# sanro.net
KiCad netlist of a schematic drawn in EAGLE
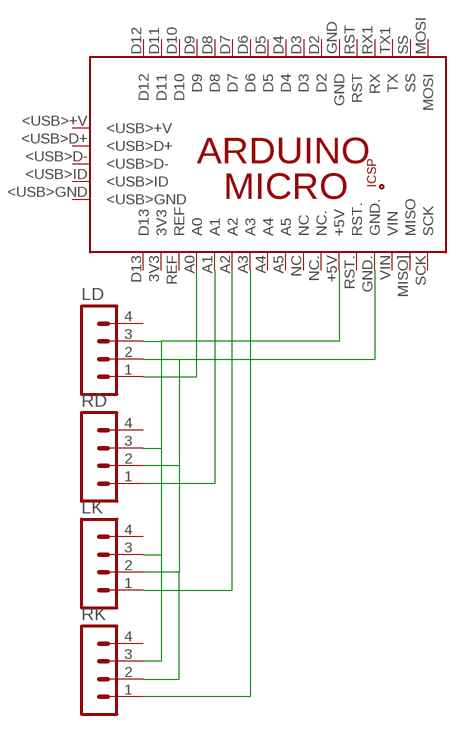
[diagram p0: schematic, sheet 1]

(export (version "E")
  (design (tool "Eeschema 10.0.6"))
  (components
    (comp (ref "LD")
      (value "MA04-1")
      (footprint "eagle-import:MA04-1")
      (libsource (lib "eagle-import") (part "MA04-1"))
    )
    (comp (ref "LK")
      (value "MA04-1")
      (footprint "eagle-import:MA04-1")
      (libsource (lib "eagle-import") (part "MA04-1"))
    )
    (comp (ref "PCB1")
      (value "ARDUINO_MICRO")
      (footprint "eagle-import:ARDUINO_MICRO")
      (libsource (lib "eagle-import") (part "ARDUINO_MICRO"))
    )
    (comp (ref "RD")
      (value "MA04-1")
      (footprint "eagle-import:MA04-1")
      (libsource (lib "eagle-import") (part "MA04-1"))
    )
    (comp (ref "RK")
      (value "MA04-1")
      (footprint "eagle-import:MA04-1")
      (libsource (lib "eagle-import") (part "MA04-1"))
    )
  )
  (nets
    (net (code "1") (name "Net-(LD-Pad1)") (class "Default")
      (node (ref "LD") (pin "1") (pinfunction "1_1") (pintype "passive"))
      (node (ref "PCB1") (pin "A0") (pinfunction "A0_A0") (pintype "bidirectional"))
    )
    (net (code "2") (name "Net-(LD-Pad2)") (class "Default")
      (node (ref "LD") (pin "2") (pinfunction "2_2") (pintype "passive"))
      (node (ref "LK") (pin "2") (pinfunction "2_2") (pintype "passive"))
      (node (ref "PCB1") (pin "GND.") (pinfunction "GND._GND.") (pintype "bidirectional"))
      (node (ref "RD") (pin "2") (pinfunction "2_2") (pintype "passive"))
      (node (ref "RK") (pin "2") (pinfunction "2_2") (pintype "passive"))
    )
    (net (code "3") (name "Net-(LD-Pad3)") (class "Default")
      (node (ref "LD") (pin "3") (pinfunction "3_3") (pintype "passive"))
      (node (ref "LK") (pin "3") (pinfunction "3_3") (pintype "passive"))
      (node (ref "PCB1") (pin "+5V") (pinfunction "+5V_+5V") (pintype "bidirectional"))
      (node (ref "RD") (pin "3") (pinfunction "3_3") (pintype "passive"))
      (node (ref "RK") (pin "3") (pinfunction "3_3") (pintype "passive"))
    )
    (net (code "4") (name "Net-(LK-Pad1)") (class "Default")
      (node (ref "LK") (pin "1") (pinfunction "1_1") (pintype "passive"))
      (node (ref "PCB1") (pin "A2") (pinfunction "A2_A2") (pintype "bidirectional"))
    )
    (net (code "5") (name "Net-(PCB1-PadA1)") (class "Default")
      (node (ref "PCB1") (pin "A1") (pinfunction "A1_A1") (pintype "bidirectional"))
      (node (ref "RD") (pin "1") (pinfunction "1_1") (pintype "passive"))
    )
    (net (code "6") (name "Net-(PCB1-PadA3)") (class "Default")
      (node (ref "PCB1") (pin "A3") (pinfunction "A3_A3") (pintype "bidirectional"))
      (node (ref "RK") (pin "1") (pinfunction "1_1") (pintype "passive"))
    )
    (net (code "7") (name "unconnected-(LD-Pad4)") (class "Default")
      (node (ref "LD") (pin "4") (pinfunction "4_4") (pintype "passive"))
    )
    (net (code "8") (name "unconnected-(LK-Pad4)") (class "Default")
      (node (ref "LK") (pin "4") (pinfunction "4_4") (pintype "passive"))
    )
    (net (code "9") (name "unconnected-(PCB1-MISO-PadMISO])") (class "Default")
      (node (ref "PCB1") (pin "MISO]") (pinfunction "MISO_MISO]") (pintype "bidirectional"))
    )
    (net (code "10") (name "unconnected-(PCB1-Pad3V3)") (class "Default")
      (node (ref "PCB1") (pin "3V3") (pinfunction "3V3_3V3") (pintype "bidirectional"))
    )
    (net (code "11") (name "unconnected-(PCB1-Pad5V)") (class "Default")
      (node (ref "PCB1") (pin "5V") (pinfunction "5V_5V") (pintype "bidirectional"))
    )
    (net (code "12") (name "unconnected-(PCB1-Pad<USB>+V)") (class "Default")
      (node (ref "PCB1") (pin "<USB>+V") (pinfunction "<USB>+V_<USB>+V") (pintype "bidirectional"))
    )
    (net (code "13") (name "unconnected-(PCB1-Pad<USB>D+)") (class "Default")
      (node (ref "PCB1") (pin "<USB>D+") (pinfunction "<USB>D+_<USB>D+") (pintype "bidirectional"))
    )
    (net (code "14") (name "unconnected-(PCB1-Pad<USB>D-)") (class "Default")
      (node (ref "PCB1") (pin "<USB>D-") (pinfunction "<USB>D-_<USB>D-") (pintype "bidirectional"))
    )
    (net (code "15") (name "unconnected-(PCB1-Pad<USB>GND)") (class "Default")
      (node (ref "PCB1") (pin "<USB>GND") (pinfunction "<USB>GND_<USB>GND") (pintype "bidirectional"))
    )
    (net (code "16") (name "unconnected-(PCB1-Pad<USB>ID)") (class "Default")
      (node (ref "PCB1") (pin "<USB>ID") (pinfunction "<USB>ID_<USB>ID") (pintype "bidirectional"))
    )
    (net (code "17") (name "unconnected-(PCB1-PadA4)") (class "Default")
      (node (ref "PCB1") (pin "A4") (pinfunction "A4_A4") (pintype "bidirectional"))
    )
    (net (code "18") (name "unconnected-(PCB1-PadA5)") (class "Default")
      (node (ref "PCB1") (pin "A5") (pinfunction "A5_A5") (pintype "bidirectional"))
    )
    (net (code "19") (name "unconnected-(PCB1-PadD2)") (class "Default")
      (node (ref "PCB1") (pin "D2") (pinfunction "D2_D2") (pintype "bidirectional"))
    )
    (net (code "20") (name "unconnected-(PCB1-PadD3)") (class "Default")
      (node (ref "PCB1") (pin "D3") (pinfunction "D3_D3") (pintype "bidirectional"))
    )
    (net (code "21") (name "unconnected-(PCB1-PadD4)") (class "Default")
      (node (ref "PCB1") (pin "D4") (pinfunction "D4_D4") (pintype "bidirectional"))
    )
    (net (code "22") (name "unconnected-(PCB1-PadD5)") (class "Default")
      (node (ref "PCB1") (pin "D5") (pinfunction "D5_D5") (pintype "bidirectional"))
    )
    (net (code "23") (name "unconnected-(PCB1-PadD6)") (class "Default")
      (node (ref "PCB1") (pin "D6") (pinfunction "D6_D6") (pintype "bidirectional"))
    )
    (net (code "24") (name "unconnected-(PCB1-PadD7)") (class "Default")
      (node (ref "PCB1") (pin "D7") (pinfunction "D7_D7") (pintype "bidirectional"))
    )
    (net (code "25") (name "unconnected-(PCB1-PadD8)") (class "Default")
      (node (ref "PCB1") (pin "D8") (pinfunction "D8_D8") (pintype "bidirectional"))
    )
    (net (code "26") (name "unconnected-(PCB1-PadD9)") (class "Default")
      (node (ref "PCB1") (pin "D9") (pinfunction "D9_D9") (pintype "bidirectional"))
    )
    (net (code "27") (name "unconnected-(PCB1-PadD10)") (class "Default")
      (node (ref "PCB1") (pin "D10") (pinfunction "D10_D10") (pintype "bidirectional"))
    )
    (net (code "28") (name "unconnected-(PCB1-PadD11)") (class "Default")
      (node (ref "PCB1") (pin "D11") (pinfunction "D11_D11") (pintype "bidirectional"))
    )
    (net (code "29") (name "unconnected-(PCB1-PadD12)") (class "Default")
      (node (ref "PCB1") (pin "D12") (pinfunction "D12_D12") (pintype "bidirectional"))
    )
    (net (code "30") (name "unconnected-(PCB1-PadD13)") (class "Default")
      (node (ref "PCB1") (pin "D13") (pinfunction "D13_D13") (pintype "bidirectional"))
    )
    (net (code "31") (name "unconnected-(PCB1-PadGND)") (class "Default")
      (node (ref "PCB1") (pin "GND") (pinfunction "GND_GND") (pintype "bidirectional"))
    )
    (net (code "32") (name "unconnected-(PCB1-PadGND_)") (class "Default")
      (node (ref "PCB1") (pin "GND_") (pinfunction "GND__GND_") (pintype "bidirectional"))
    )
    (net (code "33") (name "unconnected-(PCB1-PadMISO.)") (class "Default")
      (node (ref "PCB1") (pin "MISO.") (pinfunction "MISO._MISO.") (pintype "bidirectional"))
    )
    (net (code "34") (name "unconnected-(PCB1-PadMOSI)") (class "Default")
      (node (ref "PCB1") (pin "MOSI") (pinfunction "MOSI_MOSI") (pintype "bidirectional"))
    )
    (net (code "35") (name "unconnected-(PCB1-PadMOSI.)") (class "Default")
      (node (ref "PCB1") (pin "MOSI.") (pinfunction "MOSI._MOSI.") (pintype "bidirectional"))
    )
    (net (code "36") (name "unconnected-(PCB1-PadNC)") (class "Default")
      (node (ref "PCB1") (pin "NC") (pinfunction "NC_NC") (pintype "bidirectional"))
    )
    (net (code "37") (name "unconnected-(PCB1-PadNC.)") (class "Default")
      (node (ref "PCB1") (pin "NC.") (pinfunction "NC._NC.") (pintype "bidirectional"))
    )
    (net (code "38") (name "unconnected-(PCB1-PadREF)") (class "Default")
      (node (ref "PCB1") (pin "REF") (pinfunction "REF_REF") (pintype "bidirectional"))
    )
    (net (code "39") (name "unconnected-(PCB1-PadRESET..)") (class "Default")
      (node (ref "PCB1") (pin "RESET..") (pinfunction "RESET.._RESET..") (pintype "bidirectional"))
    )
    (net (code "40") (name "unconnected-(PCB1-PadRST)") (class "Default")
      (node (ref "PCB1") (pin "RST") (pinfunction "RST_RST") (pintype "bidirectional"))
    )
    (net (code "41") (name "unconnected-(PCB1-PadRST.)") (class "Default")
      (node (ref "PCB1") (pin "RST.") (pinfunction "RST._RST.") (pintype "bidirectional"))
    )
    (net (code "42") (name "unconnected-(PCB1-PadSCK)") (class "Default")
      (node (ref "PCB1") (pin "SCK") (pinfunction "SCK_SCK") (pintype "bidirectional"))
    )
    (net (code "43") (name "unconnected-(PCB1-PadSCK.)") (class "Default")
      (node (ref "PCB1") (pin "SCK.") (pinfunction "SCK._SCK.") (pintype "bidirectional"))
    )
    (net (code "44") (name "unconnected-(PCB1-PadSS)") (class "Default")
      (node (ref "PCB1") (pin "SS") (pinfunction "SS_SS") (pintype "bidirectional"))
    )
    (net (code "45") (name "unconnected-(PCB1-PadVIN)") (class "Default")
      (node (ref "PCB1") (pin "VIN") (pinfunction "VIN_VIN") (pintype "bidirectional"))
    )
    (net (code "46") (name "unconnected-(PCB1-RX-PadRX1)") (class "Default")
      (node (ref "PCB1") (pin "RX1") (pinfunction "RX_RX1") (pintype "bidirectional"))
    )
    (net (code "47") (name "unconnected-(PCB1-TX-PadTX1)") (class "Default")
      (node (ref "PCB1") (pin "TX1") (pinfunction "TX_TX1") (pintype "bidirectional"))
    )
    (net (code "48") (name "unconnected-(RD-Pad4)") (class "Default")
      (node (ref "RD") (pin "4") (pinfunction "4_4") (pintype "passive"))
    )
    (net (code "49") (name "unconnected-(RK-Pad4)") (class "Default")
      (node (ref "RK") (pin "4") (pinfunction "4_4") (pintype "passive"))
    )
  )
)
